# 05_-_CPU_-_POWER.net
KiCad netlist of a schematic drawn in Altium Designer
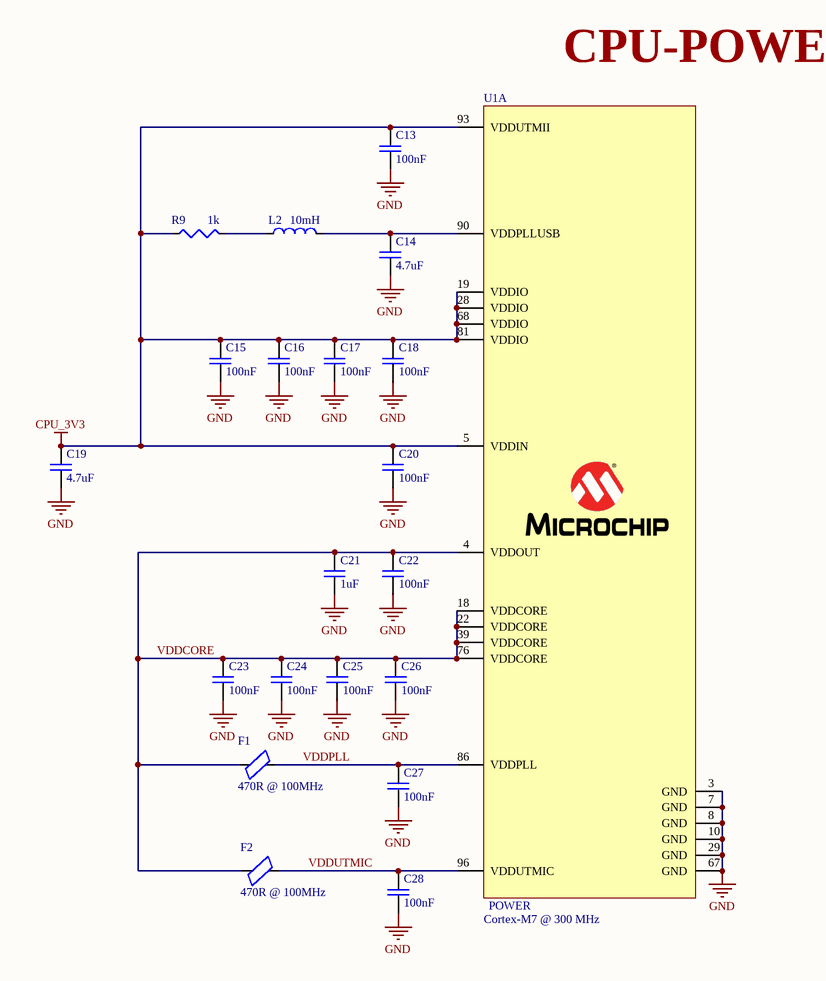
[diagram p0: [05] - CPU - POWER.SchDoc]

(export (version "E")
  (design (tool "Eeschema 10.0.6"))
  (components
    (comp (ref "C13")
      (value "100nF")
      (footprint "C0603")
      (description "C0603")
      (fields (field (name "Comment") "02016D104KAT2A"))
      (libsource (lib "Passive components") (part "02016D104KAT2A"))
    )
    (comp (ref "C14")
      (value "4.7uF")
      (footprint "C0603")
      (description "C0603")
      (fields (field (name "Comment") "02016D104KAT2A"))
      (libsource (lib "Passive components") (part "02016D104KAT2A"))
    )
    (comp (ref "C15")
      (value "100nF")
      (footprint "C0603")
      (description "C0603")
      (fields (field (name "Comment") "02016D104KAT2A"))
      (libsource (lib "Passive components") (part "02016D104KAT2A"))
    )
    (comp (ref "C16")
      (value "100nF")
      (footprint "C0603")
      (description "C0603")
      (fields (field (name "Comment") "02016D104KAT2A"))
      (libsource (lib "Passive components") (part "02016D104KAT2A"))
    )
    (comp (ref "C17")
      (value "100nF")
      (footprint "C0603")
      (description "C0603")
      (fields (field (name "Comment") "02016D104KAT2A"))
      (libsource (lib "Passive components") (part "02016D104KAT2A"))
    )
    (comp (ref "C18")
      (value "100nF")
      (footprint "C0603")
      (description "C0603")
      (fields (field (name "Comment") "02016D104KAT2A"))
      (libsource (lib "Passive components") (part "02016D104KAT2A"))
    )
    (comp (ref "C19")
      (value "4.7uF")
      (footprint "C0603")
      (description "C0603")
      (fields (field (name "Comment") "02016D104KAT2A"))
      (libsource (lib "Passive components") (part "02016D104KAT2A"))
    )
    (comp (ref "C20")
      (value "100nF")
      (footprint "C0603")
      (description "C0603")
      (fields (field (name "Comment") "02016D104KAT2A"))
      (libsource (lib "Passive components") (part "02016D104KAT2A"))
    )
    (comp (ref "C21")
      (value "1uF")
      (footprint "C0603")
      (description "C0603")
      (fields (field (name "Comment") "02016D104KAT2A"))
      (libsource (lib "Passive components") (part "02016D104KAT2A"))
    )
    (comp (ref "C22")
      (value "100nF")
      (footprint "C0603")
      (description "C0603")
      (fields (field (name "Comment") "02016D104KAT2A"))
      (libsource (lib "Passive components") (part "02016D104KAT2A"))
    )
    (comp (ref "C23")
      (value "100nF")
      (footprint "C0603")
      (description "C0603")
      (fields (field (name "Comment") "02016D104KAT2A"))
      (libsource (lib "Passive components") (part "02016D104KAT2A"))
    )
    (comp (ref "C24")
      (value "100nF")
      (footprint "C0603")
      (description "C0603")
      (fields (field (name "Comment") "02016D104KAT2A"))
      (libsource (lib "Passive components") (part "02016D104KAT2A"))
    )
    (comp (ref "C25")
      (value "100nF")
      (footprint "C0603")
      (description "C0603")
      (fields (field (name "Comment") "02016D104KAT2A"))
      (libsource (lib "Passive components") (part "02016D104KAT2A"))
    )
    (comp (ref "C26")
      (value "100nF")
      (footprint "C0603")
      (description "C0603")
      (fields (field (name "Comment") "02016D104KAT2A"))
      (libsource (lib "Passive components") (part "02016D104KAT2A"))
    )
    (comp (ref "C27")
      (value "100nF")
      (footprint "C0603")
      (description "C0603")
      (fields (field (name "Comment") "02016D104KAT2A"))
      (libsource (lib "Passive components") (part "02016D104KAT2A"))
    )
    (comp (ref "C28")
      (value "100nF")
      (footprint "C0603")
      (description "C0603")
      (fields (field (name "Comment") "02016D104KAT2A"))
      (libsource (lib "Passive components") (part "02016D104KAT2A"))
    )
    (comp (ref "F1")
      (value "470R @ 100MHz")
      (footprint "Ferrite bead 0603")
      (description "Ferrite bead 0603")
      (fields (field (name "Comment") "BLM18AG121SN1D"))
      (libsource (lib "Passive components") (part "BLM18AG121SN1D"))
    )
    (comp (ref "F2")
      (value "470R @ 100MHz")
      (footprint "Ferrite bead 0603")
      (description "Ferrite bead 0603")
      (fields (field (name "Comment") "BLM18AG121SN1D"))
      (libsource (lib "Passive components") (part "BLM18AG121SN1D"))
    )
    (comp (ref "L2")
      (value "10mH")
      (footprint "Inductor 0603")
      (description "Inductor 0603")
      (fields (field (name "Comment") "MLZ1608A2R2WT"))
      (libsource (lib "Passive components") (part "MLZ1608A2R2WT"))
    )
    (comp (ref "R9")
      (value "1k")
      (footprint "R0603")
      (description "R0603")
      (fields (field (name "Comment") "CPF-A-0603B100KE1"))
      (libsource (lib "Passive components") (part "CPF-A-0603B100KE1"))
    )
    (comp (ref "U1")
      (value "Cortex-M7 @ 300 MHz")
      (footprint "ATSAMS70N19A-AN")
      (description "ATSAMS70N19")
      (libsource (lib "Microcontrollers") (part "ATSAMS70N19A-AN"))
    )
  )
  (nets
    (net (code "1") (name "/VDDCORE") (class "Default")
      (node (ref "C21") (pin "2") (pinfunction "2_2") (pintype "passive"))
      (node (ref "C22") (pin "2") (pinfunction "2_2") (pintype "passive"))
      (node (ref "C23") (pin "2") (pinfunction "2_2") (pintype "passive"))
      (node (ref "C24") (pin "2") (pinfunction "2_2") (pintype "passive"))
      (node (ref "C25") (pin "2") (pinfunction "2_2") (pintype "passive"))
      (node (ref "C26") (pin "2") (pinfunction "2_2") (pintype "passive"))
      (node (ref "F1") (pin "1") (pinfunction "1_1") (pintype "passive"))
      (node (ref "F2") (pin "1") (pinfunction "1_1") (pintype "passive"))
      (node (ref "U1") (pin "18") (pinfunction "VDDCORE_18") (pintype "power_in"))
      (node (ref "U1") (pin "22") (pinfunction "VDDCORE_22") (pintype "power_in"))
      (node (ref "U1") (pin "39") (pinfunction "VDDCORE_39") (pintype "power_in"))
      (node (ref "U1") (pin "4") (pinfunction "VDDOUT_4") (pintype "power_in"))
      (node (ref "U1") (pin "76") (pinfunction "VDDCORE_76") (pintype "power_in"))
    )
    (net (code "2") (name "/VDDPLL") (class "Default")
      (node (ref "C27") (pin "2") (pinfunction "2_2") (pintype "passive"))
      (node (ref "F1") (pin "2") (pinfunction "2_2") (pintype "passive"))
      (node (ref "U1") (pin "86") (pinfunction "VDDPLL_86") (pintype "power_in"))
    )
    (net (code "3") (name "/VDDUTMIC") (class "Default")
      (node (ref "C28") (pin "2") (pinfunction "2_2") (pintype "passive"))
      (node (ref "F2") (pin "2") (pinfunction "2_2") (pintype "passive"))
      (node (ref "U1") (pin "96") (pinfunction "VDDUTMIC_96") (pintype "power_in"))
    )
    (net (code "4") (name "CPU_3V3") (class "Default")
      (node (ref "C13") (pin "2") (pinfunction "2_2") (pintype "passive"))
      (node (ref "C15") (pin "2") (pinfunction "2_2") (pintype "passive"))
      (node (ref "C16") (pin "2") (pinfunction "2_2") (pintype "passive"))
      (node (ref "C17") (pin "2") (pinfunction "2_2") (pintype "passive"))
      (node (ref "C18") (pin "2") (pinfunction "2_2") (pintype "passive"))
      (node (ref "C19") (pin "2") (pinfunction "2_2") (pintype "passive"))
      (node (ref "C20") (pin "2") (pinfunction "2_2") (pintype "passive"))
      (node (ref "R9") (pin "1") (pinfunction "1_1") (pintype "passive"))
      (node (ref "U1") (pin "19") (pinfunction "VDDIO_19") (pintype "power_in"))
      (node (ref "U1") (pin "28") (pinfunction "VDDIO_28") (pintype "power_in"))
      (node (ref "U1") (pin "5") (pinfunction "VDDIN_5") (pintype "power_in"))
      (node (ref "U1") (pin "68") (pinfunction "VDDIO_68") (pintype "power_in"))
      (node (ref "U1") (pin "81") (pinfunction "VDDIO_81") (pintype "power_in"))
      (node (ref "U1") (pin "93") (pinfunction "VDDUTMII_93") (pintype "power_in"))
    )
    (net (code "5") (name "GND") (class "Default")
      (node (ref "C13") (pin "1") (pinfunction "1_1") (pintype "passive"))
      (node (ref "C14") (pin "1") (pinfunction "1_1") (pintype "passive"))
      (node (ref "C15") (pin "1") (pinfunction "1_1") (pintype "passive"))
      (node (ref "C16") (pin "1") (pinfunction "1_1") (pintype "passive"))
      (node (ref "C17") (pin "1") (pinfunction "1_1") (pintype "passive"))
      (node (ref "C18") (pin "1") (pinfunction "1_1") (pintype "passive"))
      (node (ref "C19") (pin "1") (pinfunction "1_1") (pintype "passive"))
      (node (ref "C20") (pin "1") (pinfunction "1_1") (pintype "passive"))
      (node (ref "C21") (pin "1") (pinfunction "1_1") (pintype "passive"))
      (node (ref "C22") (pin "1") (pinfunction "1_1") (pintype "passive"))
      (node (ref "C23") (pin "1") (pinfunction "1_1") (pintype "passive"))
      (node (ref "C24") (pin "1") (pinfunction "1_1") (pintype "passive"))
      (node (ref "C25") (pin "1") (pinfunction "1_1") (pintype "passive"))
      (node (ref "C26") (pin "1") (pinfunction "1_1") (pintype "passive"))
      (node (ref "C27") (pin "1") (pinfunction "1_1") (pintype "passive"))
      (node (ref "C28") (pin "1") (pinfunction "1_1") (pintype "passive"))
      (node (ref "U1") (pin "10") (pinfunction "GND_10") (pintype "power_in"))
      (node (ref "U1") (pin "29") (pinfunction "GND_29") (pintype "power_in"))
      (node (ref "U1") (pin "3") (pinfunction "GND_3") (pintype "power_in"))
      (node (ref "U1") (pin "67") (pinfunction "GND_67") (pintype "power_in"))
      (node (ref "U1") (pin "7") (pinfunction "GND_7") (pintype "power_in"))
      (node (ref "U1") (pin "8") (pinfunction "GND_8") (pintype "power_in"))
    )
    (net (code "6") (name "Net-(L2-Pad1)") (class "Default")
      (node (ref "L2") (pin "1") (pinfunction "1_1") (pintype "passive"))
      (node (ref "R9") (pin "2") (pinfunction "2_2") (pintype "passive"))
    )
    (net (code "7") (name "Net-(U1A-VDDPLLUSB)") (class "Default")
      (node (ref "C14") (pin "2") (pinfunction "2_2") (pintype "passive"))
      (node (ref "L2") (pin "2") (pinfunction "2_2") (pintype "passive"))
      (node (ref "U1") (pin "90") (pinfunction "VDDPLLUSB_90") (pintype "power_in"))
    )
  )
)
